# ISEE_Soldering_Competition.net
KiCad netlist of a schematic drawn in EasyEDA Pro
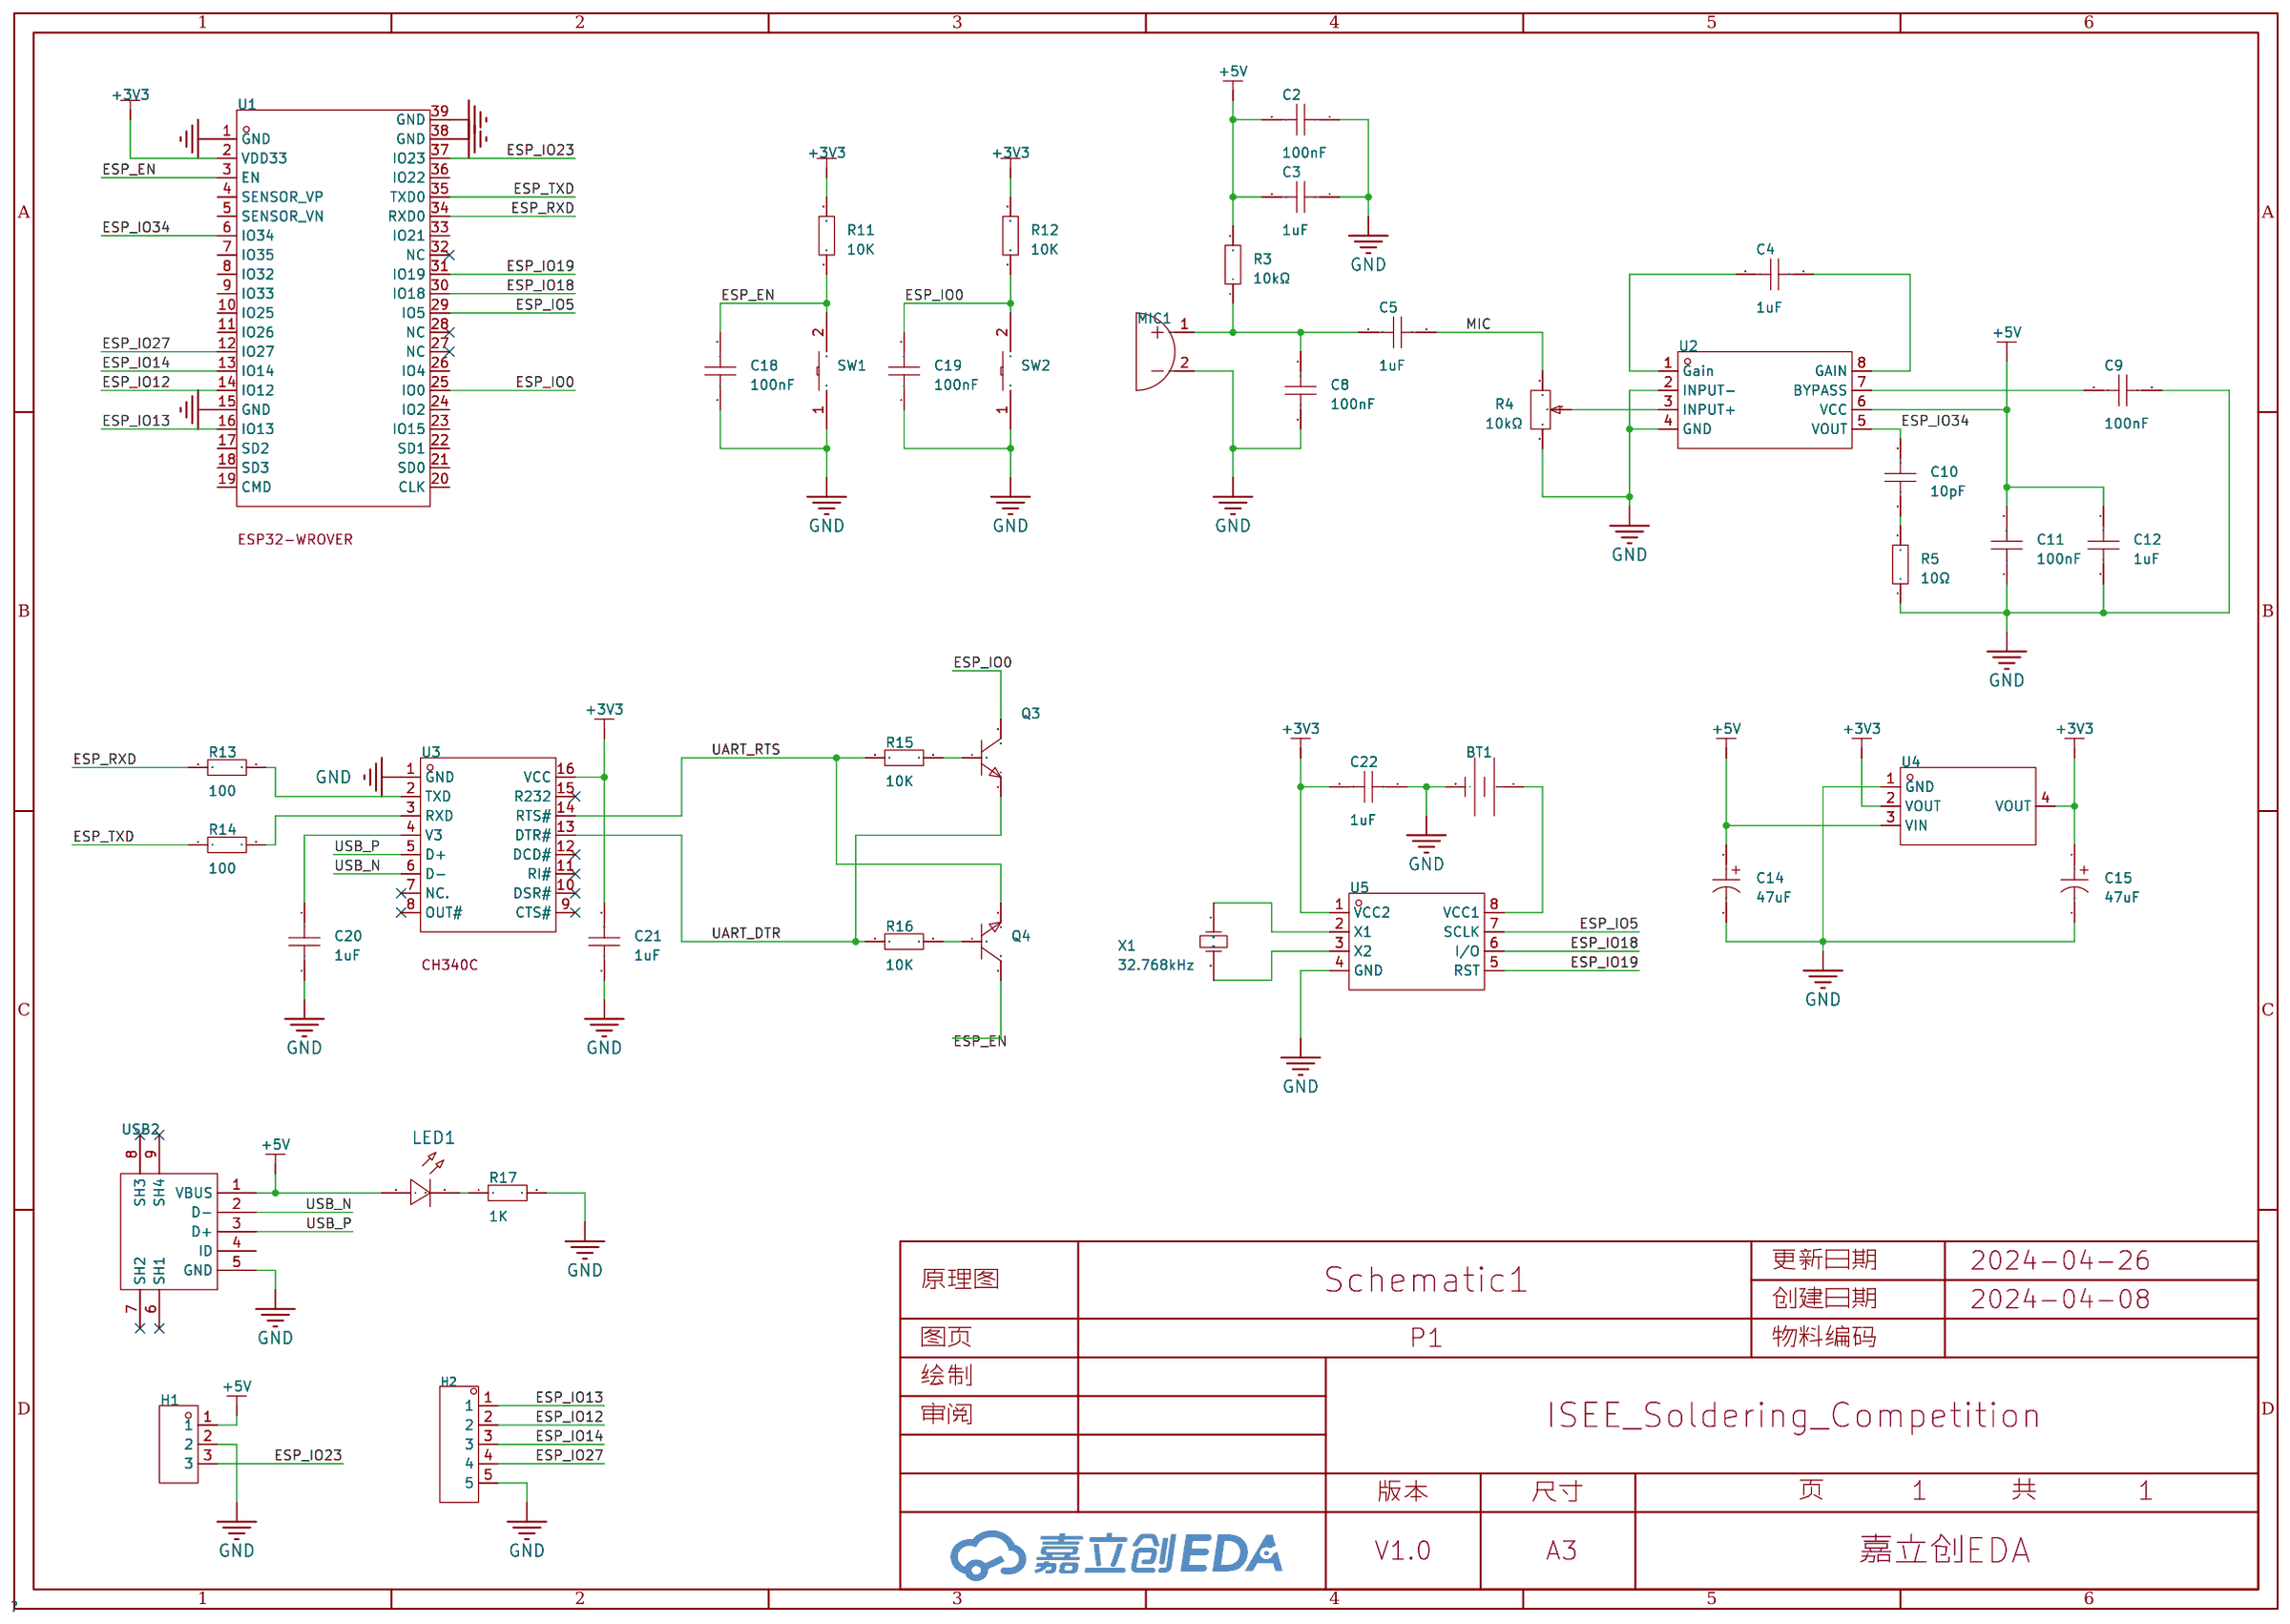
[diagram p0: schematic sheet]

(export (version "E")
  (design (tool "Eeschema 10.0.6"))
  (components
    (comp (ref "BT1")
      (value "BS-12-B3AA003")
      (footprint "easyedapro:BAT-SMD_BS-12-B3AA011")
      (description "连接器类型:电池底座;适用电池规格:CR1220;工作温度范围:-25°C~+85°C;")
      (fields (field (name "Manufacturer") "MYOUNG(美阳)"))
      (libsource (lib "easyedapro") (part "BS-12-B3AA003"))
    )
    (comp (ref "C2")
      (value "100nF")
      (footprint "easyedapro:CAP-TH_L6.5-W3.5-P5.00-D0.5")
      (description "容值:100nF;精度:±5%;额定电压:100V;介电材料:金属化聚酯;工作温度:-55°C~+85°C;")
      (fields
        (field (name "Manufacturer Part") "MPE104J100V82CL0044")
        (field (name "Manufacturer") "KNSCHA(科尼盛)")
      )
      (libsource (lib "easyedapro") (part "MPE104J100V82CL0044"))
    )
    (comp (ref "C3")
      (value "1uF")
      (footprint "easyedapro:CAP-TH_L7.5-W6.0-P5.00-D0.5")
      (description "容值:1uF;精度:±5%;额定电压:100V;介电材料:金属化聚酯;工作温度:-40°C~+110°C;")
      (fields (field (name "Manufacturer Part") "PE105J2A0502") (field (name "Manufacturer") "KYET(科雅)"))
      (libsource (lib "easyedapro") (part "PE105J2A0502"))
    )
    (comp (ref "C4")
      (value "1uF")
      (footprint "easyedapro:CAP-TH_L7.5-W6.0-P5.00-D0.5")
      (description "容值:1uF;精度:±5%;额定电压:100V;介电材料:金属化聚酯;工作温度:-40°C~+110°C;")
      (fields (field (name "Manufacturer Part") "PE105J2A0502") (field (name "Manufacturer") "KYET(科雅)"))
      (libsource (lib "easyedapro") (part "PE105J2A0502"))
    )
    (comp (ref "C5")
      (value "1uF")
      (footprint "easyedapro:CAP-TH_L7.5-W6.0-P5.00-D0.5")
      (description "容值:1uF;精度:±5%;额定电压:100V;介电材料:金属化聚酯;工作温度:-40°C~+110°C;")
      (fields (field (name "Manufacturer Part") "PE105J2A0502") (field (name "Manufacturer") "KYET(科雅)"))
      (libsource (lib "easyedapro") (part "PE105J2A0502"))
    )
    (comp (ref "C8")
      (value "100nF")
      (footprint "easyedapro:CAP-TH_L6.5-W3.5-P5.00-D0.5")
      (description "容值:100nF;精度:±5%;额定电压:100V;介电材料:金属化聚酯;工作温度:-55°C~+85°C;")
      (fields
        (field (name "Manufacturer Part") "MPE104J100V82CL0044")
        (field (name "Manufacturer") "KNSCHA(科尼盛)")
      )
      (libsource (lib "easyedapro") (part "MPE104J100V82CL0044"))
    )
    (comp (ref "C9")
      (value "100nF")
      (footprint "easyedapro:CAP-TH_L6.5-W3.5-P5.00-D0.5")
      (description "容值:100nF;精度:±5%;额定电压:100V;介电材料:金属化聚酯;工作温度:-55°C~+85°C;")
      (fields
        (field (name "Manufacturer Part") "MPE104J100V82CL0044")
        (field (name "Manufacturer") "KNSCHA(科尼盛)")
      )
      (libsource (lib "easyedapro") (part "MPE104J100V82CL0044"))
    )
    (comp (ref "C10")
      (value "10pF")
      (footprint "easyedapro:CAP-TH_L5.5-W2.5-P5.00-D1.0")
      (description "容值:10pF;精度:±10%;额定电压:1kV;温度系数:NP0;")
      (fields (field (name "Manufacturer Part") "N06A1B100KN0B0S0N0") (field (name "Manufacturer") "STE(松田)"))
      (libsource (lib "easyedapro") (part "N06A1B100KN0B0S0N0"))
    )
    (comp (ref "C11")
      (value "100nF")
      (footprint "easyedapro:CAP-TH_L6.5-W3.5-P5.00-D0.5")
      (description "容值:100nF;精度:±5%;额定电压:100V;介电材料:金属化聚酯;工作温度:-55°C~+85°C;")
      (fields
        (field (name "Manufacturer Part") "MPE104J100V82CL0044")
        (field (name "Manufacturer") "KNSCHA(科尼盛)")
      )
      (libsource (lib "easyedapro") (part "MPE104J100V82CL0044"))
    )
    (comp (ref "C12")
      (value "1uF")
      (footprint "easyedapro:CAP-TH_L7.5-W6.0-P5.00-D0.5")
      (description "容值:1uF;精度:±5%;额定电压:100V;介电材料:金属化聚酯;工作温度:-40°C~+110°C;")
      (fields (field (name "Manufacturer Part") "PE105J2A0502") (field (name "Manufacturer") "KYET(科雅)"))
      (libsource (lib "easyedapro") (part "PE105J2A0502"))
    )
    (comp (ref "C14")
      (value "47uF")
      (footprint "easyedapro:CAP-TH_BD6.3-P3.50-D0.5-FD")
      (description "容值:47uF;精度:±20%;额定电压:50V;纹波电流:180mA@100kHz;等效串联电阻:-;")
      (fields (field (name "Manufacturer Part") "03EC0571") (field (name "Manufacturer") "KNSCHA(科尼盛)"))
      (libsource (lib "easyedapro") (part "03EC0571"))
    )
    (comp (ref "C15")
      (value "47uF")
      (footprint "easyedapro:CAP-TH_BD6.3-P3.50-D0.5-FD")
      (description "容值:47uF;精度:±20%;额定电压:50V;纹波电流:180mA@100kHz;等效串联电阻:-;")
      (fields (field (name "Manufacturer Part") "03EC0571") (field (name "Manufacturer") "KNSCHA(科尼盛)"))
      (libsource (lib "easyedapro") (part "03EC0571"))
    )
    (comp (ref "C18")
      (value "100nF")
      (footprint "easyedapro:C0603")
      (libsource (lib "easyedapro") (part "CapAcitance"))
    )
    (comp (ref "C19")
      (value "100nF")
      (footprint "easyedapro:C0603")
      (libsource (lib "easyedapro") (part "CapAcitance"))
    )
    (comp (ref "C20")
      (value "1uF")
      (footprint "easyedapro:C0603")
      (libsource (lib "easyedapro") (part "CapAcitance"))
    )
    (comp (ref "C21")
      (value "1uF")
      (footprint "easyedapro:C0603")
      (libsource (lib "easyedapro") (part "CapAcitance"))
    )
    (comp (ref "C22")
      (value "1uF")
      (footprint "easyedapro:C0603")
      (libsource (lib "easyedapro") (part "CapAcitance"))
    )
    (comp (ref "H1")
      (value "~")
      (footprint "easyedapro:HDR-TH_3P-P2.54-V-M")
      (libsource (lib "easyedapro") (part "PZ254V-11-03P_C2937625"))
    )
    (comp (ref "H2")
      (value "~")
      (footprint "easyedapro:HDR-TH_5P-P2.54-V-M")
      (libsource (lib "easyedapro") (part "MTP125-1105S1"))
    )
    (comp (ref "LED1")
      (value "~")
      (footprint "easyedapro:LED_0603")
      (libsource (lib "easyedapro") (part "LED_R"))
    )
    (comp (ref "MIC1")
      (value "GMI4527P-2C-64db")
      (footprint "easyedapro:MIC-TH_BD4.5-P1.60-D0.40-L-FD")
      (fields (field (name "Manufacturer") "INGHAi(赢海)"))
      (libsource (lib "easyedapro") (part "GMI4527P-2C-64DB"))
    )
    (comp (ref "Q3")
      (value "SS8050")
      (footprint "easyedapro:SOT-23-3_L2.9-W1.3-P1.90-LS2.4-BR")
      (description "晶体管类型:NPN;集电极电流(Ic):1.5A;集射极击穿电压(Vceo):25V;功率(Pd):300mW;直流电流增益(hFE@Ic,Vce):200@100mA,1V;")
      (fields (field (name "Manufacturer") "CJ(江苏长电/长晶)"))
      (libsource (lib "easyedapro") (part "SS8050_C2150"))
    )
    (comp (ref "Q4")
      (value "SS8050")
      (footprint "easyedapro:SOT-23-3_L2.9-W1.3-P1.90-LS2.4-BR")
      (description "晶体管类型:NPN;集电极电流(Ic):1.5A;集射极击穿电压(Vceo):25V;功率(Pd):300mW;直流电流增益(hFE@Ic,Vce):200@100mA,1V;")
      (fields (field (name "Manufacturer") "CJ(江苏长电/长晶)"))
      (libsource (lib "easyedapro") (part "SS8050_C2150"))
    )
    (comp (ref "R3")
      (value "10kΩ")
      (footprint "easyedapro:Res_1/8W")
      (libsource (lib "easyedapro") (part "电阻"))
    )
    (comp (ref "R4")
      (value "10kΩ")
      (footprint "easyedapro:RES-ADJ-TH_3P-L9.5-W9.5-P2.50-L_3386P")
      (description "阻值:20kΩ;精度:±10%;")
      (fields (field (name "Manufacturer Part") "3386P-1-203") (field (name "Manufacturer") "BOCHEN(博晨)"))
      (libsource (lib "easyedapro") (part "3386P-1-203_C330584"))
    )
    (comp (ref "R5")
      (value "10Ω")
      (footprint "easyedapro:Res_1/8W")
      (libsource (lib "easyedapro") (part "电阻"))
    )
    (comp (ref "R11")
      (value "10K")
      (footprint "easyedapro:Res_1/8W")
      (libsource (lib "easyedapro") (part "电阻"))
    )
    (comp (ref "R12")
      (value "10K")
      (footprint "easyedapro:Res_1/8W")
      (libsource (lib "easyedapro") (part "电阻"))
    )
    (comp (ref "R13")
      (value "100")
      (footprint "easyedapro:Res_1/8W")
      (libsource (lib "easyedapro") (part "电阻"))
    )
    (comp (ref "R14")
      (value "100")
      (footprint "easyedapro:Res_1/8W")
      (libsource (lib "easyedapro") (part "电阻"))
    )
    (comp (ref "R15")
      (value "10K")
      (footprint "easyedapro:Res_1/8W")
      (libsource (lib "easyedapro") (part "电阻"))
    )
    (comp (ref "R16")
      (value "10K")
      (footprint "easyedapro:Res_1/8W")
      (libsource (lib "easyedapro") (part "电阻"))
    )
    (comp (ref "R17")
      (value "1K")
      (footprint "easyedapro:Res_1/8W")
      (libsource (lib "easyedapro") (part "电阻"))
    )
    (comp (ref "SW1")
      (value "TS-1101-C-W")
      (footprint "easyedapro:SW-SMD_L6.0-W3.3-LS8.0")
      (fields (field (name "Manufacturer") "XKB Connectivity(中国星坤)"))
      (libsource (lib "easyedapro") (part "TS-1101-C-W"))
    )
    (comp (ref "SW2")
      (value "TS-1101-C-W")
      (footprint "easyedapro:SW-SMD_L6.0-W3.3-LS8.0")
      (fields (field (name "Manufacturer") "XKB Connectivity(中国星坤)"))
      (libsource (lib "easyedapro") (part "TS-1101-C-W"))
    )
    (comp (ref "U1")
      (value "2.4GHz")
      (footprint "easyedapro:WIFIM-SMD_39P-L31.4-W18.0-P1.27")
      (description "核心处理器:ESP32-D0WDQ6芯片;频率:2.4GHz;发射功率:20dBm;")
      (fields (field (name "Manufacturer Part") "ESP32-WROVER") (field (name "Manufacturer") "ESPRESSIF(乐鑫)"))
      (libsource (lib "easyedapro") (part "ESP32-WROVER_C503590"))
    )
    (comp (ref "U2")
      (value "LM386M-1")
      (footprint "easyedapro:SOP-8_L4.9-W3.9-P1.27-LS6.0-BL")
      (fields (field (name "Manufacturer") "Slkor(萨科微)"))
      (libsource (lib "easyedapro") (part "LM386M-1"))
    )
    (comp (ref "U3")
      (value "CH340C")
      (footprint "easyedapro:SOP-16_L10.0-W3.9-P1.27-LS6.0-BL")
      (description "应用功能:收发器;接口协议:USB 2.0;数据速率:2Mbps;")
      (fields (field (name "Manufacturer Part") "CH340C") (field (name "Manufacturer") "WCH(南京沁恒)"))
      (libsource (lib "easyedapro") (part "CH340C"))
    )
    (comp (ref "U4")
      (value "AMS1117-3.3")
      (footprint "easyedapro:SOT-223-3_L6.5-W3.4-P2.30-LS7.0-BR")
      (description "输出类型:固定;最大输入电压:-;输出电压:3.3V;最大输出电流:1A;电源纹波抑制比(PSRR):72dB@(120Hz);输出极性:正极;")
      (fields (field (name "Manufacturer") "AMS"))
      (libsource (lib "easyedapro") (part "AMS1117-3.3"))
    )
    (comp (ref "U5")
      (value "DS1302ZM/TR")
      (footprint "easyedapro:SOP-8_L4.9-W3.9-P1.27-LS6.0-BL")
      (description "工业级 具有涓细电流充电能力的低功耗实时时钟芯片")
      (fields (field (name "Manufacturer") "HGSEMI(华冠)"))
      (libsource (lib "easyedapro") (part "DS1302ZM"))
    )
    (comp (ref "USB2")
      (value "MicroXNJ")
      (footprint "easyedapro:MICRO-USB-SMD_MICROXNJ")
      (description "连接器类型:Micro-B;标准:USB 2.0;公母:母;端口数量:1;触点数量:5P;安装方式:卧贴;额定电流 - 电源:1A;工作温度范围:-20°C~+85°C;")
      (fields (field (name "Manufacturer") "SHOU HAN(首韩)"))
      (libsource (lib "easyedapro") (part "MICROXNJ"))
    )
    (comp (ref "X1")
      (value "32.768kHz")
      (footprint "easyedapro:OSC-TH_BD3.1-P0.8-D0.3")
      (description "晶振类型:直插晶振;频率:32.768kHz;常温频差:±10ppm;外接负载电容:12.5pF;频率稳定度(全温):-;")
      (fields (field (name "Manufacturer Part") "X308032768KGB2SC") (field (name "Manufacturer") "YXC(扬兴晶振)"))
      (libsource (lib "easyedapro") (part "X308032768KGB2SC"))
    )
  )
  (nets
    (net (code "1") (name "+3V3") (class "Default")
      (node (ref "C15") (pin "1") (pinfunction "1_1") (pintype "input"))
      (node (ref "C21") (pin "2") (pinfunction "2_2") (pintype "input"))
      (node (ref "C22") (pin "2") (pinfunction "2_2") (pintype "input"))
      (node (ref "R11") (pin "2") (pinfunction "2_2") (pintype "input"))
      (node (ref "R12") (pin "2") (pinfunction "2_2") (pintype "input"))
      (node (ref "U1") (pin "2") (pinfunction "VDD33_2") (pintype "unspecified"))
      (node (ref "U3") (pin "16") (pinfunction "VCC_16") (pintype "unspecified"))
      (node (ref "U4") (pin "2") (pinfunction "VOUT_2") (pintype "unspecified"))
      (node (ref "U4") (pin "4") (pinfunction "VOUT_4") (pintype "unspecified"))
      (node (ref "U5") (pin "1") (pinfunction "VCC2_1") (pintype "unspecified"))
    )
    (net (code "2") (name "+5V") (class "Default")
      (node (ref "C11") (pin "2") (pinfunction "2_2") (pintype "unspecified"))
      (node (ref "C12") (pin "1") (pinfunction "1_1") (pintype "unspecified"))
      (node (ref "C14") (pin "1") (pinfunction "1_1") (pintype "input"))
      (node (ref "C2") (pin "2") (pinfunction "2_2") (pintype "unspecified"))
      (node (ref "C3") (pin "2") (pinfunction "2_2") (pintype "unspecified"))
      (node (ref "H1") (pin "1") (pinfunction "1_1") (pintype "input"))
      (node (ref "LED1") (pin "2") (pinfunction "A_2") (pintype "input"))
      (node (ref "R3") (pin "2") (pinfunction "2_2") (pintype "input"))
      (node (ref "U2") (pin "6") (pinfunction "VCC_6") (pintype "unspecified"))
      (node (ref "U4") (pin "3") (pinfunction "VIN_3") (pintype "unspecified"))
      (node (ref "USB2") (pin "1") (pinfunction "VBUS_1") (pintype "unspecified"))
    )
    (net (code "3") (name "/ESP_EN") (class "Default")
      (node (ref "C18") (pin "2") (pinfunction "2_2") (pintype "input"))
      (node (ref "Q4") (pin "3") (pinfunction "C_3") (pintype "unspecified"))
      (node (ref "R11") (pin "1") (pinfunction "1_1") (pintype "input"))
      (node (ref "SW1") (pin "2") (pinfunction "2_2") (pintype "unspecified"))
      (node (ref "U1") (pin "3") (pinfunction "EN_3") (pintype "unspecified"))
    )
    (net (code "4") (name "/ESP_IO0") (class "Default")
      (node (ref "C19") (pin "2") (pinfunction "2_2") (pintype "input"))
      (node (ref "Q3") (pin "3") (pinfunction "C_3") (pintype "unspecified"))
      (node (ref "R12") (pin "1") (pinfunction "1_1") (pintype "input"))
      (node (ref "SW2") (pin "2") (pinfunction "2_2") (pintype "unspecified"))
      (node (ref "U1") (pin "25") (pinfunction "IO0_25") (pintype "unspecified"))
    )
    (net (code "5") (name "/ESP_IO5") (class "Default")
      (node (ref "U1") (pin "29") (pinfunction "IO5_29") (pintype "unspecified"))
      (node (ref "U5") (pin "7") (pinfunction "SCLK_7") (pintype "unspecified"))
    )
    (net (code "6") (name "/ESP_IO12") (class "Default")
      (node (ref "H2") (pin "2") (pinfunction "2_2") (pintype "input"))
      (node (ref "U1") (pin "14") (pinfunction "IO12_14") (pintype "unspecified"))
    )
    (net (code "7") (name "/ESP_IO13") (class "Default")
      (node (ref "H2") (pin "1") (pinfunction "1_1") (pintype "input"))
      (node (ref "U1") (pin "16") (pinfunction "IO13_16") (pintype "unspecified"))
    )
    (net (code "8") (name "/ESP_IO14") (class "Default")
      (node (ref "H2") (pin "3") (pinfunction "3_3") (pintype "input"))
      (node (ref "U1") (pin "13") (pinfunction "IO14_13") (pintype "unspecified"))
    )
    (net (code "9") (name "/ESP_IO18") (class "Default")
      (node (ref "U1") (pin "30") (pinfunction "IO18_30") (pintype "unspecified"))
      (node (ref "U5") (pin "6") (pinfunction "I/O_6") (pintype "unspecified"))
    )
    (net (code "10") (name "/ESP_IO19") (class "Default")
      (node (ref "U1") (pin "31") (pinfunction "IO19_31") (pintype "unspecified"))
      (node (ref "U5") (pin "5") (pinfunction "RST_5") (pintype "unspecified"))
    )
    (net (code "11") (name "/ESP_IO23") (class "Default")
      (node (ref "H1") (pin "3") (pinfunction "3_3") (pintype "input"))
      (node (ref "U1") (pin "37") (pinfunction "IO23_37") (pintype "unspecified"))
    )
    (net (code "12") (name "/ESP_IO27") (class "Default")
      (node (ref "H2") (pin "4") (pinfunction "4_4") (pintype "input"))
      (node (ref "U1") (pin "12") (pinfunction "IO27_12") (pintype "unspecified"))
    )
    (net (code "13") (name "/ESP_IO34") (class "Default")
      (node (ref "C10") (pin "2") (pinfunction "2_2") (pintype "unspecified"))
      (node (ref "U1") (pin "6") (pinfunction "IO34_6") (pintype "unspecified"))
      (node (ref "U2") (pin "5") (pinfunction "VOUT_5") (pintype "unspecified"))
    )
    (net (code "14") (name "/ESP_RXD") (class "Default")
      (node (ref "R13") (pin "1") (pinfunction "1_1") (pintype "input"))
      (node (ref "U1") (pin "34") (pinfunction "RXD0_34") (pintype "unspecified"))
    )
    (net (code "15") (name "/ESP_TXD") (class "Default")
      (node (ref "R14") (pin "1") (pinfunction "1_1") (pintype "input"))
      (node (ref "U1") (pin "35") (pinfunction "TXD0_35") (pintype "unspecified"))
    )
    (net (code "16") (name "/MIC") (class "Default")
      (node (ref "C5") (pin "1") (pinfunction "1_1") (pintype "unspecified"))
      (node (ref "R4") (pin "1") (pinfunction "1_1") (pintype "input"))
    )
    (net (code "17") (name "/UART_DTR") (class "Default")
      (node (ref "Q3") (pin "2") (pinfunction "E_2") (pintype "unspecified"))
      (node (ref "R16") (pin "1") (pinfunction "1_1") (pintype "input"))
      (node (ref "U3") (pin "13") (pinfunction "DTR#_13") (pintype "unspecified"))
    )
    (net (code "18") (name "/UART_RTS") (class "Default")
      (node (ref "Q4") (pin "2") (pinfunction "E_2") (pintype "unspecified"))
      (node (ref "R15") (pin "1") (pinfunction "1_1") (pintype "input"))
      (node (ref "U3") (pin "14") (pinfunction "RTS#_14") (pintype "unspecified"))
    )
    (net (code "19") (name "/USB_N") (class "Default")
      (node (ref "U3") (pin "6") (pinfunction "D-_6") (pintype "unspecified"))
      (node (ref "USB2") (pin "2") (pinfunction "D-_2") (pintype "unspecified"))
    )
    (net (code "20") (name "/USB_P") (class "Default")
      (node (ref "U3") (pin "5") (pinfunction "D+_5") (pintype "unspecified"))
      (node (ref "USB2") (pin "3") (pinfunction "D+_3") (pintype "unspecified"))
    )
    (net (code "21") (name "GND") (class "Default")
      (node (ref "BT1") (pin "2") (pinfunction "-_2") (pintype "unspecified"))
      (node (ref "C11") (pin "1") (pinfunction "1_1") (pintype "unspecified"))
      (node (ref "C12") (pin "2") (pinfunction "2_2") (pintype "unspecified"))
      (node (ref "C14") (pin "2") (pinfunction "2_2") (pintype "input"))
      (node (ref "C15") (pin "2") (pinfunction "2_2") (pintype "input"))
      (node (ref "C18") (pin "1") (pinfunction "1_1") (pintype "input"))
      (node (ref "C19") (pin "1") (pinfunction "1_1") (pintype "input"))
      (node (ref "C2") (pin "1") (pinfunction "1_1") (pintype "unspecified"))
      (node (ref "C20") (pin "1") (pinfunction "1_1") (pintype "input"))
      (node (ref "C21") (pin "1") (pinfunction "1_1") (pintype "input"))
      (node (ref "C22") (pin "1") (pinfunction "1_1") (pintype "input"))
      (node (ref "C3") (pin "1") (pinfunction "1_1") (pintype "unspecified"))
      (node (ref "C8") (pin "2") (pinfunction "2_2") (pintype "unspecified"))
      (node (ref "C9") (pin "1") (pinfunction "1_1") (pintype "unspecified"))
      (node (ref "H1") (pin "2") (pinfunction "2_2") (pintype "input"))
      (node (ref "H2") (pin "5") (pinfunction "5_5") (pintype "input"))
      (node (ref "MIC1") (pin "2") (pinfunction "2_2") (pintype "input"))
      (node (ref "R17") (pin "2") (pinfunction "2_2") (pintype "input"))
      (node (ref "R4") (pin "3") (pinfunction "3_3") (pintype "input"))
      (node (ref "R5") (pin "1") (pinfunction "1_1") (pintype "input"))
      (node (ref "SW1") (pin "1") (pinfunction "1_1") (pintype "unspecified"))
      (node (ref "SW2") (pin "1") (pinfunction "1_1") (pintype "unspecified"))
      (node (ref "U1") (pin "1") (pinfunction "GND_1") (pintype "unspecified"))
      (node (ref "U1") (pin "15") (pinfunction "GND_15") (pintype "unspecified"))
      (node (ref "U1") (pin "38") (pinfunction "GND_38") (pintype "unspecified"))
      (node (ref "U1") (pin "39") (pinfunction "GND_39") (pintype "unspecified"))
      (node (ref "U2") (pin "2") (pinfunction "INPUT-_2") (pintype "unspecified"))
      (node (ref "U2") (pin "4") (pinfunction "GND_4") (pintype "unspecified"))
      (node (ref "U3") (pin "1") (pinfunction "GND_1") (pintype "unspecified"))
      (node (ref "U4") (pin "1") (pinfunction "GND_1") (pintype "unspecified"))
      (node (ref "U5") (pin "4") (pinfunction "GND_4") (pintype "unspecified"))
      (node (ref "USB2") (pin "5") (pinfunction "GND_5") (pintype "unspecified"))
    )
    (net (code "22") (name "Net-(BT1-+)") (class "Default")
      (node (ref "BT1") (pin "1") (pinfunction "+_1") (pintype "unspecified"))
      (node (ref "U5") (pin "8") (pinfunction "VCC1_8") (pintype "unspecified"))
    )
    (net (code "23") (name "Net-(C5-Pad2)") (class "Default")
      (node (ref "C5") (pin "2") (pinfunction "2_2") (pintype "unspecified"))
      (node (ref "C8") (pin "1") (pinfunction "1_1") (pintype "unspecified"))
      (node (ref "MIC1") (pin "1") (pinfunction "1_1") (pintype "input"))
      (node (ref "R3") (pin "1") (pinfunction "1_1") (pintype "input"))
    )
    (net (code "24") (name "Net-(C10-Pad1)") (class "Default")
      (node (ref "C10") (pin "1") (pinfunction "1_1") (pintype "unspecified"))
      (node (ref "R5") (pin "2") (pinfunction "2_2") (pintype "input"))
    )
    (net (code "25") (name "Net-(LED1-C)") (class "Default")
      (node (ref "LED1") (pin "1") (pinfunction "C_1") (pintype "input"))
      (node (ref "R17") (pin "1") (pinfunction "1_1") (pintype "input"))
    )
    (net (code "26") (name "Net-(Q3-B)") (class "Default")
      (node (ref "Q3") (pin "1") (pinfunction "B_1") (pintype "unspecified"))
      (node (ref "R15") (pin "2") (pinfunction "2_2") (pintype "input"))
    )
    (net (code "27") (name "Net-(Q4-B)") (class "Default")
      (node (ref "Q4") (pin "1") (pinfunction "B_1") (pintype "unspecified"))
      (node (ref "R16") (pin "2") (pinfunction "2_2") (pintype "input"))
    )
    (net (code "28") (name "Net-(U2-BYPASS)") (class "Default")
      (node (ref "C9") (pin "2") (pinfunction "2_2") (pintype "unspecified"))
      (node (ref "U2") (pin "7") (pinfunction "BYPASS_7") (pintype "unspecified"))
    )
    (net (code "29") (name "Net-(U2-GAIN)") (class "Default")
      (node (ref "C4") (pin "1") (pinfunction "1_1") (pintype "unspecified"))
      (node (ref "U2") (pin "8") (pinfunction "GAIN_8") (pintype "unspecified"))
    )
    (net (code "30") (name "Net-(U2-Gain)") (class "Default")
      (node (ref "C4") (pin "2") (pinfunction "2_2") (pintype "unspecified"))
      (node (ref "U2") (pin "1") (pinfunction "Gain_1") (pintype "unspecified"))
    )
    (net (code "31") (name "Net-(U2-INPUT+)") (class "Default")
      (node (ref "R4") (pin "2") (pinfunction "2_2") (pintype "input"))
      (node (ref "U2") (pin "3") (pinfunction "INPUT+_3") (pintype "unspecified"))
    )
    (net (code "32") (name "Net-(U3-RXD)") (class "Default")
      (node (ref "R14") (pin "2") (pinfunction "2_2") (pintype "input"))
      (node (ref "U3") (pin "3") (pinfunction "RXD_3") (pintype "unspecified"))
    )
    (net (code "33") (name "Net-(U3-TXD)") (class "Default")
      (node (ref "R13") (pin "2") (pinfunction "2_2") (pintype "input"))
      (node (ref "U3") (pin "2") (pinfunction "TXD_2") (pintype "unspecified"))
    )
    (net (code "34") (name "Net-(U3-V3)") (class "Default")
      (node (ref "C20") (pin "2") (pinfunction "2_2") (pintype "input"))
      (node (ref "U3") (pin "4") (pinfunction "V3_4") (pintype "unspecified"))
    )
    (net (code "35") (name "Net-(U5-X1)") (class "Default")
      (node (ref "U5") (pin "2") (pinfunction "X1_2") (pintype "unspecified"))
      (node (ref "X1") (pin "1") (pinfunction "OSC1_1") (pintype "unspecified"))
    )
    (net (code "36") (name "Net-(U5-X2)") (class "Default")
      (node (ref "U5") (pin "3") (pinfunction "X2_3") (pintype "unspecified"))
      (node (ref "X1") (pin "2") (pinfunction "OSC2_2") (pintype "unspecified"))
    )
    (net (code "37") (name "unconnected-(U1-CLK-Pad20)") (class "Default")
      (node (ref "U1") (pin "20") (pinfunction "CLK_20") (pintype "unspecified"))
    )
    (net (code "38") (name "unconnected-(U1-CMD-Pad19)") (class "Default")
      (node (ref "U1") (pin "19") (pinfunction "CMD_19") (pintype "unspecified"))
    )
    (net (code "39") (name "unconnected-(U1-IO2-Pad24)") (class "Default")
      (node (ref "U1") (pin "24") (pinfunction "IO2_24") (pintype "unspecified"))
    )
    (net (code "40") (name "unconnected-(U1-IO4-Pad26)") (class "Default")
      (node (ref "U1") (pin "26") (pinfunction "IO4_26") (pintype "unspecified"))
    )
    (net (code "41") (name "unconnected-(U1-IO15-Pad23)") (class "Default")
      (node (ref "U1") (pin "23") (pinfunction "IO15_23") (pintype "unspecified"))
    )
    (net (code "42") (name "unconnected-(U1-IO21-Pad33)") (class "Default")
      (node (ref "U1") (pin "33") (pinfunction "IO21_33") (pintype "unspecified"))
    )
    (net (code "43") (name "unconnected-(U1-IO22-Pad36)") (class "Default")
      (node (ref "U1") (pin "36") (pinfunction "IO22_36") (pintype "unspecified"))
    )
    (net (code "44") (name "unconnected-(U1-IO25-Pad10)") (class "Default")
      (node (ref "U1") (pin "10") (pinfunction "IO25_10") (pintype "unspecified"))
    )
    (net (code "45") (name "unconnected-(U1-IO26-Pad11)") (class "Default")
      (node (ref "U1") (pin "11") (pinfunction "IO26_11") (pintype "unspecified"))
    )
    (net (code "46") (name "unconnected-(U1-IO32-Pad8)") (class "Default")
      (node (ref "U1") (pin "8") (pinfunction "IO32_8") (pintype "unspecified"))
    )
    (net (code "47") (name "unconnected-(U1-IO33-Pad9)") (class "Default")
      (node (ref "U1") (pin "9") (pinfunction "IO33_9") (pintype "unspecified"))
    )
    (net (code "48") (name "unconnected-(U1-IO35-Pad7)") (class "Default")
      (node (ref "U1") (pin "7") (pinfunction "IO35_7") (pintype "unspecified"))
    )
    (net (code "49") (name "unconnected-(U1-NC-Pad27)") (class "Default")
      (node (ref "U1") (pin "27") (pinfunction "NC_27") (pintype "unspecified+no_connect"))
    )
    (net (code "50") (name "unconnected-(U1-NC-Pad28)") (class "Default")
      (node (ref "U1") (pin "28") (pinfunction "NC_28") (pintype "unspecified+no_connect"))
    )
    (net (code "51") (name "unconnected-(U1-NC-Pad32)") (class "Default")
      (node (ref "U1") (pin "32") (pinfunction "NC_32") (pintype "unspecified+no_connect"))
    )
    (net (code "52") (name "unconnected-(U1-SD0-Pad21)") (class "Default")
      (node (ref "U1") (pin "21") (pinfunction "SD0_21") (pintype "unspecified"))
    )
    (net (code "53") (name "unconnected-(U1-SD1-Pad22)") (class "Default")
      (node (ref "U1") (pin "22") (pinfunction "SD1_22") (pintype "unspecified"))
    )
    (net (code "54") (name "unconnected-(U1-SD2-Pad17)") (class "Default")
      (node (ref "U1") (pin "17") (pinfunction "SD2_17") (pintype "unspecified"))
    )
    (net (code "55") (name "unconnected-(U1-SD3-Pad18)") (class "Default")
      (node (ref "U1") (pin "18") (pinfunction "SD3_18") (pintype "unspecified"))
    )
    (net (code "56") (name "unconnected-(U1-SENSOR_VN-Pad5)") (class "Default")
      (node (ref "U1") (pin "5") (pinfunction "SENSOR_VN_5") (pintype "unspecified"))
    )
    (net (code "57") (name "unconnected-(U1-SENSOR_VP-Pad4)") (class "Default")
      (node (ref "U1") (pin "4") (pinfunction "SENSOR_VP_4") (pintype "unspecified"))
    )
    (net (code "58") (name "unconnected-(U3-CTS#-Pad9)") (class "Default")
      (node (ref "U3") (pin "9") (pinfunction "CTS#_9") (pintype "unspecified+no_connect"))
    )
    (net (code "59") (name "unconnected-(U3-DCD#-Pad12)") (class "Default")
      (node (ref "U3") (pin "12") (pinfunction "DCD#_12") (pintype "unspecified+no_connect"))
    )
    (net (code "60") (name "unconnected-(U3-DSR#-Pad10)") (class "Default")
      (node (ref "U3") (pin "10") (pinfunction "DSR#_10") (pintype "unspecified+no_connect"))
    )
    (net (code "61") (name "unconnected-(U3-NC.-Pad7)") (class "Default")
      (node (ref "U3") (pin "7") (pinfunction "NC._7") (pintype "unspecified+no_connect"))
    )
    (net (code "62") (name "unconnected-(U3-OUT#-Pad8)") (class "Default")
      (node (ref "U3") (pin "8") (pinfunction "OUT#_8") (pintype "unspecified+no_connect"))
    )
    (net (code "63") (name "unconnected-(U3-R232-Pad15)") (class "Default")
      (node (ref "U3") (pin "15") (pinfunction "R232_15") (pintype "unspecified+no_connect"))
    )
    (net (code "64") (name "unconnected-(U3-RI#-Pad11)") (class "Default")
      (node (ref "U3") (pin "11") (pinfunction "RI#_11") (pintype "unspecified+no_connect"))
    )
    (net (code "65") (name "unconnected-(USB2-ID-Pad4)") (class "Default")
      (node (ref "USB2") (pin "4") (pinfunction "ID_4") (pintype "unspecified"))
    )
    (net (code "66") (name "unconnected-(USB2-SH1-Pad6)") (class "Default")
      (node (ref "USB2") (pin "6") (pinfunction "SH1_6") (pintype "unspecified+no_connect"))
    )
    (net (code "67") (name "unconnected-(USB2-SH2-Pad7)") (class "Default")
      (node (ref "USB2") (pin "7") (pinfunction "SH2_7") (pintype "unspecified+no_connect"))
    )
    (net (code "68") (name "unconnected-(USB2-SH3-Pad8)") (class "Default")
      (node (ref "USB2") (pin "8") (pinfunction "SH3_8") (pintype "unspecified+no_connect"))
    )
    (net (code "69") (name "unconnected-(USB2-SH4-Pad9)") (class "Default")
      (node (ref "USB2") (pin "9") (pinfunction "SH4_9") (pintype "unspecified+no_connect"))
    )
  )
)
